# RHD2164_GGmod.net
KiCad netlist of a schematic drawn in EAGLE
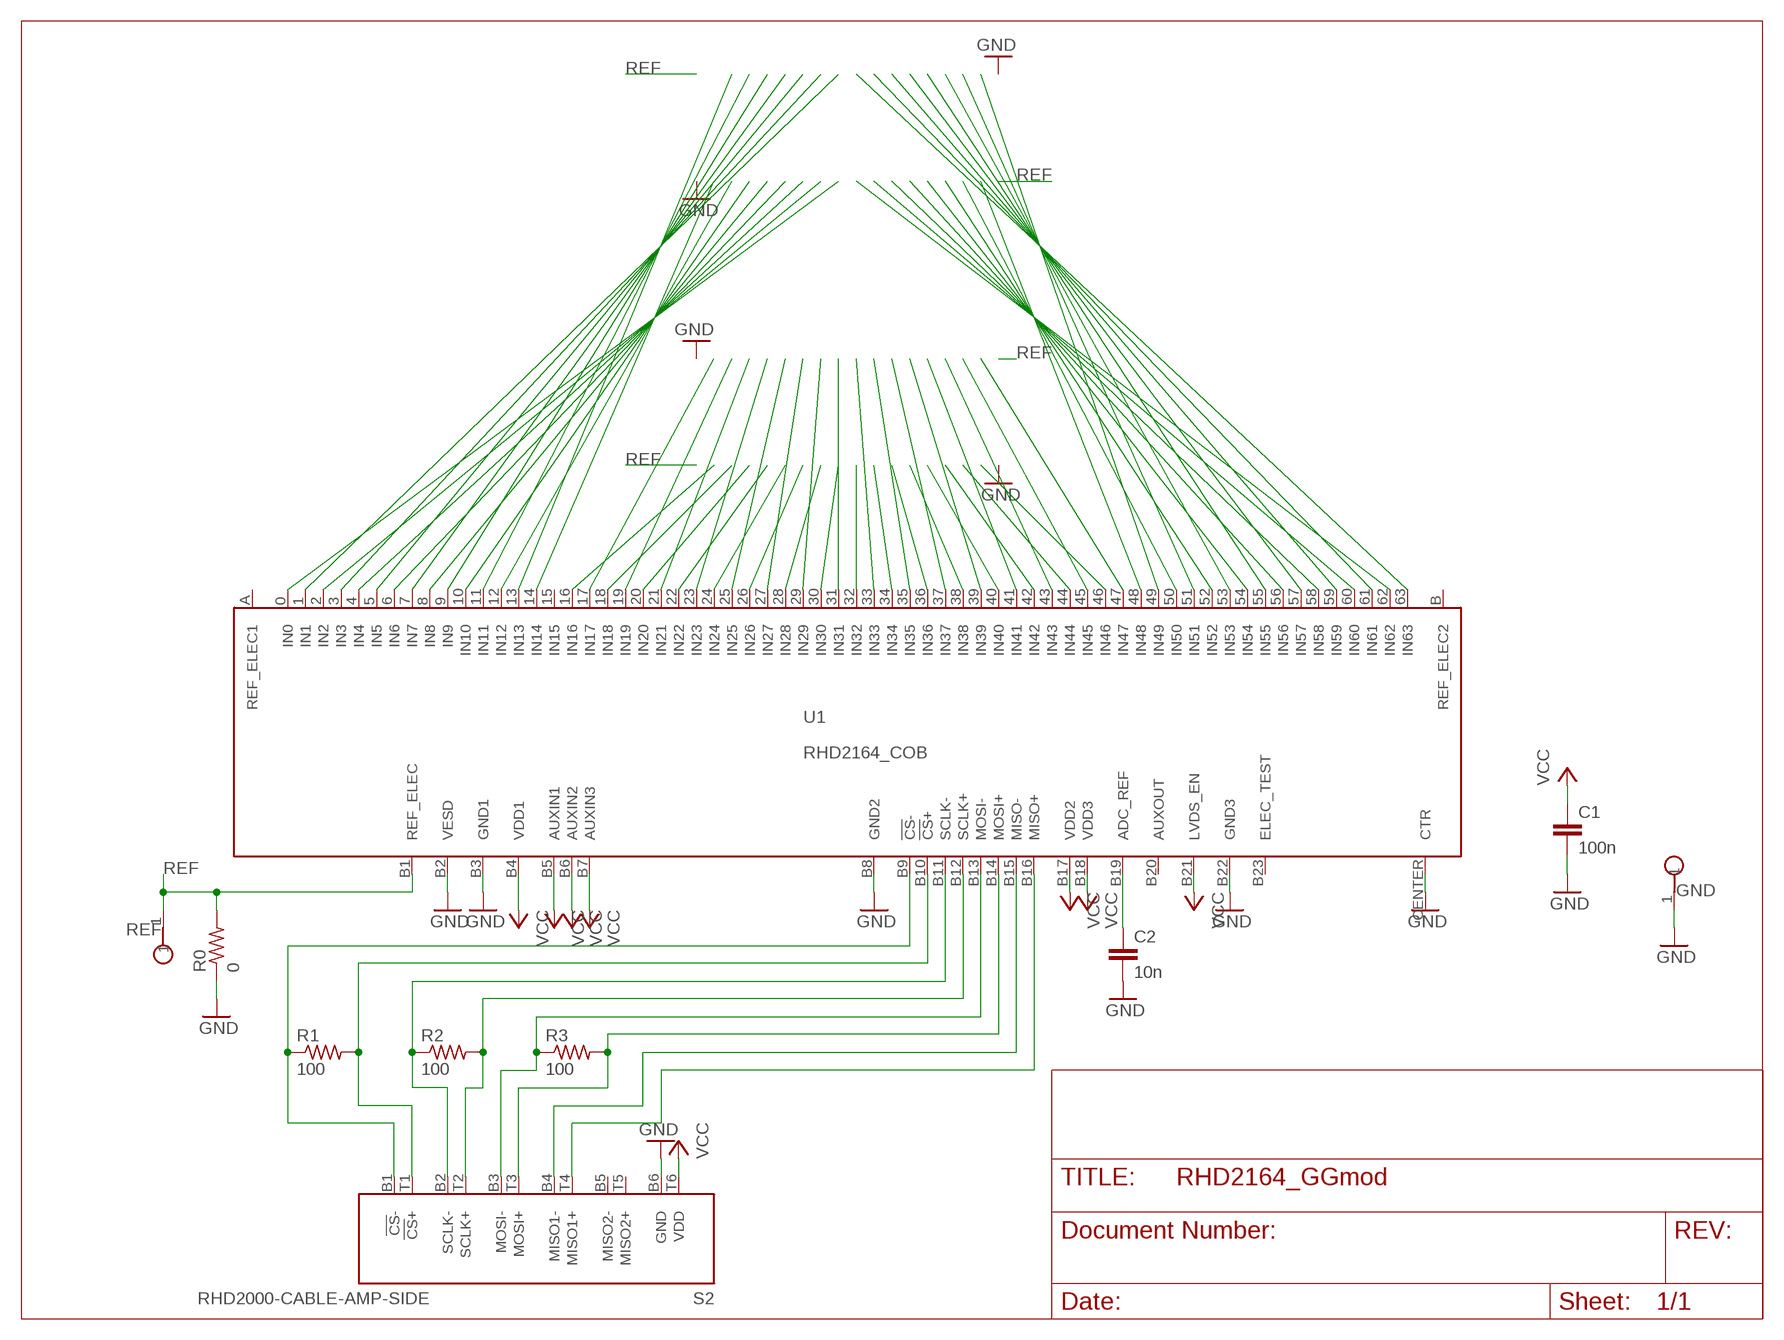
[diagram p0: schematic, sheet 1]

(export (version "E")
  (design (tool "Eeschema 10.0.6"))
  (components
    (comp (ref "C1")
      (value "100n")
      (footprint "eagle-import:0402")
      (libsource (lib "eagle-import") (part "C_0402"))
    )
    (comp (ref "C2")
      (value "10n")
      (footprint "eagle-import:0201")
      (libsource (lib "eagle-import") (part "C_0201"))
    )
    (comp (ref "GND")
      (value "TESTPOINT_SMALL")
      (footprint "eagle-import:TESTPOINT_SMALL")
      (libsource (lib "eagle-import") (part "TESTPOINT_SMALL"))
    )
    (comp (ref "R0")
      (value "0")
      (footprint "eagle-import:0402")
      (libsource (lib "eagle-import") (part "R_0402"))
    )
    (comp (ref "R1")
      (value "100")
      (footprint "eagle-import:0201")
      (libsource (lib "eagle-import") (part "R_0201"))
    )
    (comp (ref "R2")
      (value "100")
      (footprint "eagle-import:0201")
      (libsource (lib "eagle-import") (part "R_0201"))
    )
    (comp (ref "R3")
      (value "100")
      (footprint "eagle-import:0201")
      (libsource (lib "eagle-import") (part "R_0201"))
    )
    (comp (ref "REF")
      (value "TESTPOINT_SMALL")
      (footprint "eagle-import:TESTPOINT_SMALL")
      (libsource (lib "eagle-import") (part "TESTPOINT_SMALL"))
    )
    (comp (ref "S2")
      (value "RHD2000-CABLE-AMP-SIDE")
      (footprint "eagle-import:OMNETICS_PZN-12-AA")
      (libsource (lib "eagle-import") (part "RHD2000-CABLE-AMP-SIDE"))
    )
    (comp (ref "U1")
      (value "RHD2164_COB")
      (footprint "eagle-import:RHD2164_COB")
      (libsource (lib "eagle-import") (part "RHD2164_COB"))
    )
  )
  (nets
    (net (code "1") (name "/REF") (class "Default")
      (node (ref "R0") (pin "2") (pinfunction "2_2") (pintype "passive"))
      (node (ref "REF") (pin "1") (pinfunction "1_1") (pintype "passive"))
      (node (ref "U1") (pin "B1") (pinfunction "REF_ELEC_B1") (pintype "input"))
    )
    (net (code "2") (name "GND") (class "Default")
      (node (ref "C1") (pin "2") (pinfunction "2_2") (pintype "passive"))
      (node (ref "C2") (pin "2") (pinfunction "2_2") (pintype "passive"))
      (node (ref "GND") (pin "1") (pinfunction "1_1") (pintype "passive"))
      (node (ref "R0") (pin "1") (pinfunction "1_1") (pintype "passive"))
      (node (ref "S2") (pin "B6") (pinfunction "GND_B6") (pintype "power_in"))
      (node (ref "U1") (pin "B2") (pinfunction "VESD_B2") (pintype "power_in"))
      (node (ref "U1") (pin "B22") (pinfunction "GND3_B22") (pintype "power_in"))
      (node (ref "U1") (pin "B3") (pinfunction "GND1_B3") (pintype "power_in"))
      (node (ref "U1") (pin "B8") (pinfunction "GND2_B8") (pintype "power_in"))
      (node (ref "U1") (pin "CENTER") (pinfunction "CTR_CENTER") (pintype "power_in"))
    )
    (net (code "3") (name "Net-(S2-MISO1+)") (class "Default")
      (node (ref "S2") (pin "T4") (pinfunction "MISO1+_T4") (pintype "bidirectional"))
      (node (ref "U1") (pin "B16") (pinfunction "MISO+_B16") (pintype "output"))
    )
    (net (code "4") (name "Net-(S2-MISO1-)") (class "Default")
      (node (ref "S2") (pin "B4") (pinfunction "MISO1-_B4") (pintype "bidirectional"))
      (node (ref "U1") (pin "B15") (pinfunction "MISO-_B15") (pintype "output"))
    )
    (net (code "5") (name "Net-(S2-MOSI+)") (class "Default")
      (node (ref "R3") (pin "2") (pinfunction "2_2") (pintype "passive"))
      (node (ref "S2") (pin "T3") (pinfunction "MOSI+_T3") (pintype "bidirectional"))
      (node (ref "U1") (pin "B14") (pinfunction "MOSI+_B14") (pintype "input"))
    )
    (net (code "6") (name "Net-(S2-MOSI-)") (class "Default")
      (node (ref "R3") (pin "1") (pinfunction "1_1") (pintype "passive"))
      (node (ref "S2") (pin "B3") (pinfunction "MOSI-_B3") (pintype "bidirectional"))
      (node (ref "U1") (pin "B13") (pinfunction "MOSI-_B13") (pintype "input"))
    )
    (net (code "7") (name "Net-(S2-SCLK+)") (class "Default")
      (node (ref "R2") (pin "2") (pinfunction "2_2") (pintype "passive"))
      (node (ref "S2") (pin "T2") (pinfunction "SCLK+_T2") (pintype "bidirectional"))
      (node (ref "U1") (pin "B12") (pinfunction "SCLK+_B12") (pintype "input"))
    )
    (net (code "8") (name "Net-(S2-SCLK-)") (class "Default")
      (node (ref "R2") (pin "1") (pinfunction "1_1") (pintype "passive"))
      (node (ref "S2") (pin "B2") (pinfunction "SCLK-_B2") (pintype "bidirectional"))
      (node (ref "U1") (pin "B11") (pinfunction "SCLK-_B11") (pintype "input"))
    )
    (net (code "9") (name "Net-(S2-~{CS}+)") (class "Default")
      (node (ref "R1") (pin "2") (pinfunction "2_2") (pintype "passive"))
      (node (ref "S2") (pin "T1") (pinfunction "~{CS}+_T1") (pintype "bidirectional"))
      (node (ref "U1") (pin "B10") (pinfunction "~{CS}+_B10") (pintype "input"))
    )
    (net (code "10") (name "Net-(S2-~{CS}-)") (class "Default")
      (node (ref "R1") (pin "1") (pinfunction "1_1") (pintype "passive"))
      (node (ref "S2") (pin "B1") (pinfunction "~{CS}-_B1") (pintype "bidirectional"))
      (node (ref "U1") (pin "B9") (pinfunction "~{CS}-_B9") (pintype "input"))
    )
    (net (code "11") (name "Net-(U1-ADC_REF)") (class "Default")
      (node (ref "C2") (pin "1") (pinfunction "1_1") (pintype "passive"))
      (node (ref "U1") (pin "B19") (pinfunction "ADC_REF_B19") (pintype "passive"))
    )
    (net (code "12") (name "VCC") (class "Default")
      (node (ref "C1") (pin "1") (pinfunction "1_1") (pintype "passive"))
      (node (ref "S2") (pin "T6") (pinfunction "VDD_T6") (pintype "bidirectional"))
      (node (ref "U1") (pin "B17") (pinfunction "VDD2_B17") (pintype "power_in"))
      (node (ref "U1") (pin "B18") (pinfunction "VDD3_B18") (pintype "power_in"))
      (node (ref "U1") (pin "B21") (pinfunction "LVDS_EN_B21") (pintype "input"))
      (node (ref "U1") (pin "B4") (pinfunction "VDD1_B4") (pintype "power_in"))
      (node (ref "U1") (pin "B5") (pinfunction "AUXIN1_B5") (pintype "input"))
      (node (ref "U1") (pin "B6") (pinfunction "AUXIN2_B6") (pintype "input"))
      (node (ref "U1") (pin "B7") (pinfunction "AUXIN3_B7") (pintype "input"))
    )
    (net (code "13") (name "unconnected-(S2-MISO2+-PadT5)") (class "Default")
      (node (ref "S2") (pin "T5") (pinfunction "MISO2+_T5") (pintype "bidirectional"))
    )
    (net (code "14") (name "unconnected-(S2-MISO2--PadB5)") (class "Default")
      (node (ref "S2") (pin "B5") (pinfunction "MISO2-_B5") (pintype "bidirectional"))
    )
    (net (code "15") (name "unconnected-(U1-AUXOUT-PadB20)") (class "Default")
      (node (ref "U1") (pin "B20") (pinfunction "AUXOUT_B20") (pintype "tri_state"))
    )
    (net (code "16") (name "unconnected-(U1-ELEC_TEST-PadB23)") (class "Default")
      (node (ref "U1") (pin "B23") (pinfunction "ELEC_TEST_B23") (pintype "input"))
    )
    (net (code "17") (name "unconnected-(U1-IN0-Pad0)") (class "Default")
      (node (ref "U1") (pin "0") (pinfunction "IN0_0") (pintype "input"))
    )
    (net (code "18") (name "unconnected-(U1-IN1-Pad1)") (class "Default")
      (node (ref "U1") (pin "1") (pinfunction "IN1_1") (pintype "input"))
    )
    (net (code "19") (name "unconnected-(U1-IN2-Pad2)") (class "Default")
      (node (ref "U1") (pin "2") (pinfunction "IN2_2") (pintype "input"))
    )
    (net (code "20") (name "unconnected-(U1-IN3-Pad3)") (class "Default")
      (node (ref "U1") (pin "3") (pinfunction "IN3_3") (pintype "input"))
    )
    (net (code "21") (name "unconnected-(U1-IN4-Pad4)") (class "Default")
      (node (ref "U1") (pin "4") (pinfunction "IN4_4") (pintype "input"))
    )
    (net (code "22") (name "unconnected-(U1-IN5-Pad5)") (class "Default")
      (node (ref "U1") (pin "5") (pinfunction "IN5_5") (pintype "input"))
    )
    (net (code "23") (name "unconnected-(U1-IN6-Pad6)") (class "Default")
      (node (ref "U1") (pin "6") (pinfunction "IN6_6") (pintype "input"))
    )
    (net (code "24") (name "unconnected-(U1-IN7-Pad7)") (class "Default")
      (node (ref "U1") (pin "7") (pinfunction "IN7_7") (pintype "input"))
    )
    (net (code "25") (name "unconnected-(U1-IN8-Pad8)") (class "Default")
      (node (ref "U1") (pin "8") (pinfunction "IN8_8") (pintype "input"))
    )
    (net (code "26") (name "unconnected-(U1-IN9-Pad9)") (class "Default")
      (node (ref "U1") (pin "9") (pinfunction "IN9_9") (pintype "input"))
    )
    (net (code "27") (name "unconnected-(U1-IN10-Pad10)") (class "Default")
      (node (ref "U1") (pin "10") (pinfunction "IN10_10") (pintype "input"))
    )
    (net (code "28") (name "unconnected-(U1-IN11-Pad11)") (class "Default")
      (node (ref "U1") (pin "11") (pinfunction "IN11_11") (pintype "input"))
    )
    (net (code "29") (name "unconnected-(U1-IN12-Pad12)") (class "Default")
      (node (ref "U1") (pin "12") (pinfunction "IN12_12") (pintype "input"))
    )
    (net (code "30") (name "unconnected-(U1-IN13-Pad13)") (class "Default")
      (node (ref "U1") (pin "13") (pinfunction "IN13_13") (pintype "input"))
    )
    (net (code "31") (name "unconnected-(U1-IN14-Pad14)") (class "Default")
      (node (ref "U1") (pin "14") (pinfunction "IN14_14") (pintype "input"))
    )
    (net (code "32") (name "unconnected-(U1-IN15-Pad15)") (class "Default")
      (node (ref "U1") (pin "15") (pinfunction "IN15_15") (pintype "input"))
    )
    (net (code "33") (name "unconnected-(U1-IN16-Pad16)") (class "Default")
      (node (ref "U1") (pin "16") (pinfunction "IN16_16") (pintype "input"))
    )
    (net (code "34") (name "unconnected-(U1-IN17-Pad17)") (class "Default")
      (node (ref "U1") (pin "17") (pinfunction "IN17_17") (pintype "input"))
    )
    (net (code "35") (name "unconnected-(U1-IN18-Pad18)") (class "Default")
      (node (ref "U1") (pin "18") (pinfunction "IN18_18") (pintype "input"))
    )
    (net (code "36") (name "unconnected-(U1-IN19-Pad19)") (class "Default")
      (node (ref "U1") (pin "19") (pinfunction "IN19_19") (pintype "input"))
    )
    (net (code "37") (name "unconnected-(U1-IN20-Pad20)") (class "Default")
      (node (ref "U1") (pin "20") (pinfunction "IN20_20") (pintype "input"))
    )
    (net (code "38") (name "unconnected-(U1-IN21-Pad21)") (class "Default")
      (node (ref "U1") (pin "21") (pinfunction "IN21_21") (pintype "input"))
    )
    (net (code "39") (name "unconnected-(U1-IN22-Pad22)") (class "Default")
      (node (ref "U1") (pin "22") (pinfunction "IN22_22") (pintype "input"))
    )
    (net (code "40") (name "unconnected-(U1-IN23-Pad23)") (class "Default")
      (node (ref "U1") (pin "23") (pinfunction "IN23_23") (pintype "input"))
    )
    (net (code "41") (name "unconnected-(U1-IN24-Pad24)") (class "Default")
      (node (ref "U1") (pin "24") (pinfunction "IN24_24") (pintype "input"))
    )
    (net (code "42") (name "unconnected-(U1-IN25-Pad25)") (class "Default")
      (node (ref "U1") (pin "25") (pinfunction "IN25_25") (pintype "input"))
    )
    (net (code "43") (name "unconnected-(U1-IN26-Pad26)") (class "Default")
      (node (ref "U1") (pin "26") (pinfunction "IN26_26") (pintype "input"))
    )
    (net (code "44") (name "unconnected-(U1-IN27-Pad27)") (class "Default")
      (node (ref "U1") (pin "27") (pinfunction "IN27_27") (pintype "input"))
    )
    (net (code "45") (name "unconnected-(U1-IN28-Pad28)") (class "Default")
      (node (ref "U1") (pin "28") (pinfunction "IN28_28") (pintype "input"))
    )
    (net (code "46") (name "unconnected-(U1-IN29-Pad29)") (class "Default")
      (node (ref "U1") (pin "29") (pinfunction "IN29_29") (pintype "input"))
    )
    (net (code "47") (name "unconnected-(U1-IN30-Pad30)") (class "Default")
      (node (ref "U1") (pin "30") (pinfunction "IN30_30") (pintype "input"))
    )
    (net (code "48") (name "unconnected-(U1-IN31-Pad31)") (class "Default")
      (node (ref "U1") (pin "31") (pinfunction "IN31_31") (pintype "input"))
    )
    (net (code "49") (name "unconnected-(U1-IN32-Pad32)") (class "Default")
      (node (ref "U1") (pin "32") (pinfunction "IN32_32") (pintype "input"))
    )
    (net (code "50") (name "unconnected-(U1-IN33-Pad33)") (class "Default")
      (node (ref "U1") (pin "33") (pinfunction "IN33_33") (pintype "input"))
    )
    (net (code "51") (name "unconnected-(U1-IN34-Pad34)") (class "Default")
      (node (ref "U1") (pin "34") (pinfunction "IN34_34") (pintype "input"))
    )
    (net (code "52") (name "unconnected-(U1-IN35-Pad35)") (class "Default")
      (node (ref "U1") (pin "35") (pinfunction "IN35_35") (pintype "input"))
    )
    (net (code "53") (name "unconnected-(U1-IN36-Pad36)") (class "Default")
      (node (ref "U1") (pin "36") (pinfunction "IN36_36") (pintype "input"))
    )
    (net (code "54") (name "unconnected-(U1-IN37-Pad37)") (class "Default")
      (node (ref "U1") (pin "37") (pinfunction "IN37_37") (pintype "input"))
    )
    (net (code "55") (name "unconnected-(U1-IN38-Pad38)") (class "Default")
      (node (ref "U1") (pin "38") (pinfunction "IN38_38") (pintype "input"))
    )
    (net (code "56") (name "unconnected-(U1-IN39-Pad39)") (class "Default")
      (node (ref "U1") (pin "39") (pinfunction "IN39_39") (pintype "input"))
    )
    (net (code "57") (name "unconnected-(U1-IN40-Pad40)") (class "Default")
      (node (ref "U1") (pin "40") (pinfunction "IN40_40") (pintype "input"))
    )
    (net (code "58") (name "unconnected-(U1-IN41-Pad41)") (class "Default")
      (node (ref "U1") (pin "41") (pinfunction "IN41_41") (pintype "input"))
    )
    (net (code "59") (name "unconnected-(U1-IN42-Pad42)") (class "Default")
      (node (ref "U1") (pin "42") (pinfunction "IN42_42") (pintype "input"))
    )
    (net (code "60") (name "unconnected-(U1-IN43-Pad43)") (class "Default")
      (node (ref "U1") (pin "43") (pinfunction "IN43_43") (pintype "input"))
    )
    (net (code "61") (name "unconnected-(U1-IN44-Pad44)") (class "Default")
      (node (ref "U1") (pin "44") (pinfunction "IN44_44") (pintype "input"))
    )
    (net (code "62") (name "unconnected-(U1-IN45-Pad45)") (class "Default")
      (node (ref "U1") (pin "45") (pinfunction "IN45_45") (pintype "input"))
    )
    (net (code "63") (name "unconnected-(U1-IN46-Pad46)") (class "Default")
      (node (ref "U1") (pin "46") (pinfunction "IN46_46") (pintype "input"))
    )
    (net (code "64") (name "unconnected-(U1-IN47-Pad47)") (class "Default")
      (node (ref "U1") (pin "47") (pinfunction "IN47_47") (pintype "input"))
    )
    (net (code "65") (name "unconnected-(U1-IN48-Pad48)") (class "Default")
      (node (ref "U1") (pin "48") (pinfunction "IN48_48") (pintype "input"))
    )
    (net (code "66") (name "unconnected-(U1-IN49-Pad49)") (class "Default")
      (node (ref "U1") (pin "49") (pinfunction "IN49_49") (pintype "input"))
    )
    (net (code "67") (name "unconnected-(U1-IN50-Pad50)") (class "Default")
      (node (ref "U1") (pin "50") (pinfunction "IN50_50") (pintype "input"))
    )
    (net (code "68") (name "unconnected-(U1-IN51-Pad51)") (class "Default")
      (node (ref "U1") (pin "51") (pinfunction "IN51_51") (pintype "input"))
    )
    (net (code "69") (name "unconnected-(U1-IN52-Pad52)") (class "Default")
      (node (ref "U1") (pin "52") (pinfunction "IN52_52") (pintype "input"))
    )
    (net (code "70") (name "unconnected-(U1-IN53-Pad53)") (class "Default")
      (node (ref "U1") (pin "53") (pinfunction "IN53_53") (pintype "input"))
    )
    (net (code "71") (name "unconnected-(U1-IN54-Pad54)") (class "Default")
      (node (ref "U1") (pin "54") (pinfunction "IN54_54") (pintype "input"))
    )
    (net (code "72") (name "unconnected-(U1-IN55-Pad55)") (class "Default")
      (node (ref "U1") (pin "55") (pinfunction "IN55_55") (pintype "input"))
    )
    (net (code "73") (name "unconnected-(U1-IN56-Pad56)") (class "Default")
      (node (ref "U1") (pin "56") (pinfunction "IN56_56") (pintype "input"))
    )
    (net (code "74") (name "unconnected-(U1-IN57-Pad57)") (class "Default")
      (node (ref "U1") (pin "57") (pinfunction "IN57_57") (pintype "input"))
    )
    (net (code "75") (name "unconnected-(U1-IN58-Pad58)") (class "Default")
      (node (ref "U1") (pin "58") (pinfunction "IN58_58") (pintype "input"))
    )
    (net (code "76") (name "unconnected-(U1-IN59-Pad59)") (class "Default")
      (node (ref "U1") (pin "59") (pinfunction "IN59_59") (pintype "input"))
    )
    (net (code "77") (name "unconnected-(U1-IN60-Pad60)") (class "Default")
      (node (ref "U1") (pin "60") (pinfunction "IN60_60") (pintype "input"))
    )
    (net (code "78") (name "unconnected-(U1-IN61-Pad61)") (class "Default")
      (node (ref "U1") (pin "61") (pinfunction "IN61_61") (pintype "input"))
    )
    (net (code "79") (name "unconnected-(U1-IN62-Pad62)") (class "Default")
      (node (ref "U1") (pin "62") (pinfunction "IN62_62") (pintype "input"))
    )
    (net (code "80") (name "unconnected-(U1-IN63-Pad63)") (class "Default")
      (node (ref "U1") (pin "63") (pinfunction "IN63_63") (pintype "input"))
    )
    (net (code "81") (name "unconnected-(U1-REF_ELEC1-PadA)") (class "Default")
      (node (ref "U1") (pin "A") (pinfunction "REF_ELEC1_A") (pintype "input"))
    )
    (net (code "82") (name "unconnected-(U1-REF_ELEC2-PadB)") (class "Default")
      (node (ref "U1") (pin "B") (pinfunction "REF_ELEC2_B") (pintype "input"))
    )
  )
)
